# main.net
KiCad netlist of a schematic drawn in EAGLE
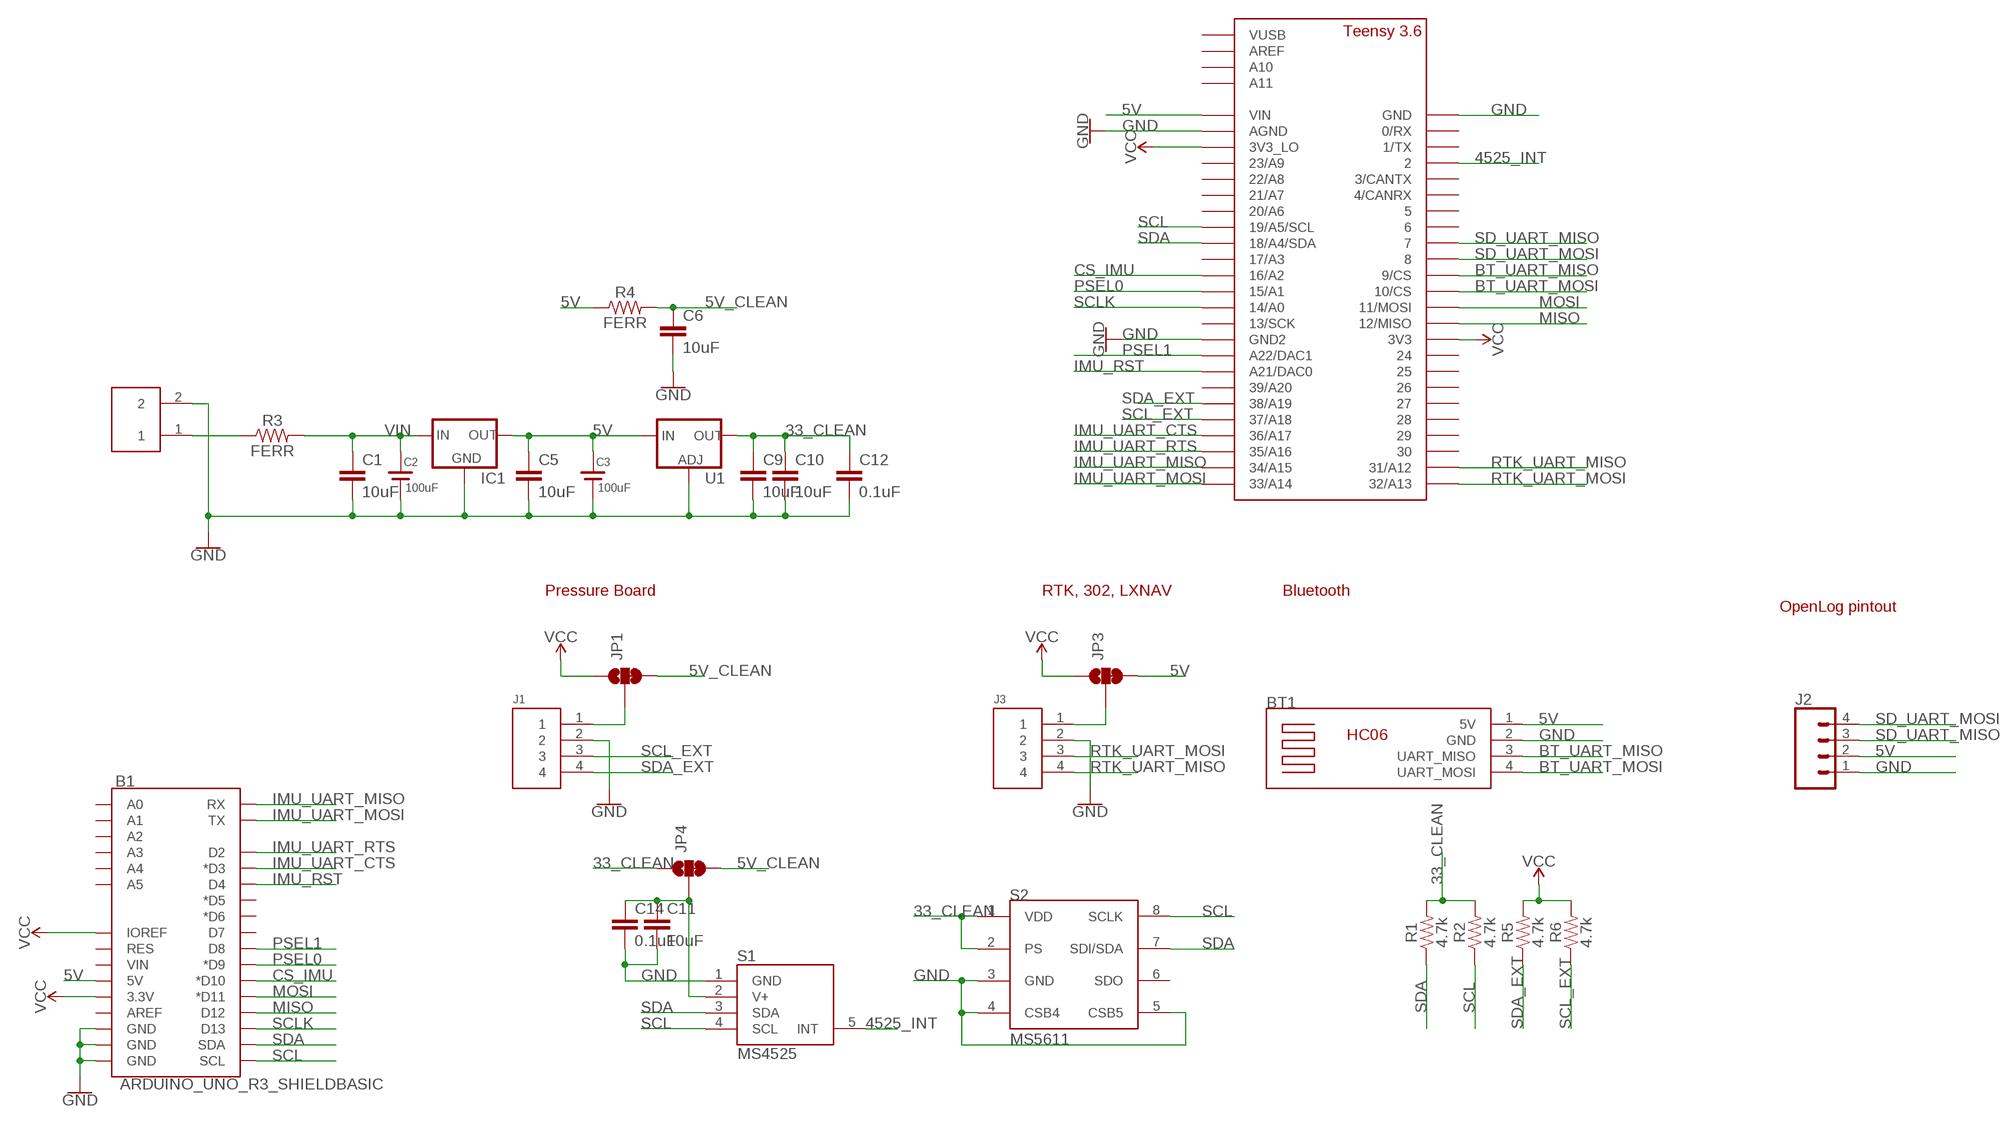
[diagram p0: schematic, sheet 1]

(export (version "E")
  (design (tool "Eeschema 10.0.6"))
  (components
    (comp (ref "B1")
      (value "ARDUINO_UNO_R3_SHIELDBASIC")
      (footprint "eagle-import:UNO_R3_SHIELD")
      (libsource (lib "eagle-import") (part "ARDUINO_UNO_R3_SHIELDBASIC"))
    )
    (comp (ref "BT1")
      (value "HC06")
      (footprint "eagle-import:HC06")
      (libsource (lib "eagle-import") (part "HC06"))
    )
    (comp (ref "C1")
      (value "10uF")
      (footprint "eagle-import:1206")
      (libsource (lib "eagle-import") (part "10UF-1206-6.3V-20%"))
    )
    (comp (ref "C2")
      (value "100uF")
      (footprint "eagle-import:CAP_8MM_35MM")
      (libsource (lib "eagle-import") (part "CAP_POLARCAP_8_DIA_35_LEAD"))
    )
    (comp (ref "C3")
      (value "100uF")
      (footprint "eagle-import:CAP_8MM_35MM")
      (libsource (lib "eagle-import") (part "CAP_POLARCAP_8_DIA_35_LEAD"))
    )
    (comp (ref "C5")
      (value "10uF")
      (footprint "eagle-import:1206")
      (libsource (lib "eagle-import") (part "10UF-1206-6.3V-20%"))
    )
    (comp (ref "C6")
      (value "10uF")
      (footprint "eagle-import:1206")
      (libsource (lib "eagle-import") (part "10UF-1206-6.3V-20%"))
    )
    (comp (ref "C9")
      (value "10uF")
      (footprint "eagle-import:1206")
      (libsource (lib "eagle-import") (part "10UF-1206-6.3V-20%"))
    )
    (comp (ref "C10")
      (value "10uF")
      (footprint "eagle-import:1206")
      (libsource (lib "eagle-import") (part "10UF-1206-6.3V-20%"))
    )
    (comp (ref "C11")
      (value "10uF")
      (footprint "eagle-import:1206")
      (libsource (lib "eagle-import") (part "10UF-1206-6.3V-20%"))
    )
    (comp (ref "C12")
      (value "0.1uF")
      (footprint "eagle-import:0603")
      (libsource (lib "eagle-import") (part "0.1UF-0603-25V-5%"))
    )
    (comp (ref "C14")
      (value "0.1uF")
      (footprint "eagle-import:0603")
      (libsource (lib "eagle-import") (part "0.1UF-0603-25V-5%"))
    )
    (comp (ref "IC1")
      (value "V_REG_78XXR-78E")
      (footprint "eagle-import:V78W")
      (libsource (lib "eagle-import") (part "V_REG_78XXR-78E"))
    )
    (comp (ref "J1")
      (value "HEADER4VALULOK")
      (footprint "eagle-import:4PINVALULOK")
      (libsource (lib "eagle-import") (part "HEADER4VALULOK"))
    )
    (comp (ref "J2")
      (value "CONN_04")
      (footprint "eagle-import:1X04")
      (libsource (lib "eagle-import") (part "CONN_04"))
    )
    (comp (ref "J3")
      (value "HEADER4VALULOK")
      (footprint "eagle-import:4PINVALULOK")
      (libsource (lib "eagle-import") (part "HEADER4VALULOK"))
    )
    (comp (ref "JP1")
      (value "JUMPER-SMT_3_1-NC_TRACE_SILK")
      (footprint "eagle-import:SMT-JUMPER_3_1-NC_TRACE_SILK")
      (libsource (lib "eagle-import") (part "JUMPER-SMT_3_1-NC_TRACE_SILK"))
    )
    (comp (ref "JP3")
      (value "JUMPER-SMT_3_1-NC_TRACE_SILK")
      (footprint "eagle-import:SMT-JUMPER_3_1-NC_TRACE_SILK")
      (libsource (lib "eagle-import") (part "JUMPER-SMT_3_1-NC_TRACE_SILK"))
    )
    (comp (ref "JP4")
      (value "JUMPER-SMT_3_1-NC_TRACE_SILK")
      (footprint "eagle-import:SMT-JUMPER_3_1-NC_TRACE_SILK")
      (libsource (lib "eagle-import") (part "JUMPER-SMT_3_1-NC_TRACE_SILK"))
    )
    (comp (ref "R1")
      (value "4.7k")
      (footprint "eagle-import:0603")
      (libsource (lib "eagle-import") (part "4.7KOHM-0603-1/10W-1%"))
    )
    (comp (ref "R2")
      (value "4.7k")
      (footprint "eagle-import:0603")
      (libsource (lib "eagle-import") (part "4.7KOHM-0603-1/10W-1%"))
    )
    (comp (ref "R3")
      (value "FERR")
      (footprint "eagle-import:1206")
      (libsource (lib "eagle-import") (part "RESISTOR1206"))
    )
    (comp (ref "R4")
      (value "FERR")
      (footprint "eagle-import:1206")
      (libsource (lib "eagle-import") (part "RESISTOR1206"))
    )
    (comp (ref "R5")
      (value "4.7k")
      (footprint "eagle-import:0603")
      (libsource (lib "eagle-import") (part "4.7KOHM-0603-1/10W-1%"))
    )
    (comp (ref "R6")
      (value "4.7k")
      (footprint "eagle-import:0603")
      (libsource (lib "eagle-import") (part "4.7KOHM-0603-1/10W-1%"))
    )
    (comp (ref "S1")
      (value "MS4525")
      (footprint "eagle-import:DIP1270W53P254L990H762Q8B")
      (libsource (lib "eagle-import") (part "MS4525MS4525DO"))
    )
    (comp (ref "S2")
      (value "MS5611")
      (footprint "eagle-import:MS5611")
      (libsource (lib "eagle-import") (part "MS5611"))
    )
    (comp (ref "U$1")
      (value "TEENSY_3.5/3.6_BASIC")
      (footprint "eagle-import:TEENSY_3.5_3.6_BASIC")
      (libsource (lib "eagle-import") (part "TEENSY_3.5/3.6_BASIC"))
    )
    (comp (ref "U$3")
      (value "HEADER2")
      (footprint "eagle-import:2PINVALULOK")
      (libsource (lib "eagle-import") (part "HEADER2"))
    )
    (comp (ref "U1")
      (value "V_REG_317SMD")
      (footprint "eagle-import:SOT223")
      (libsource (lib "eagle-import") (part "V_REG_317SMD"))
    )
  )
  (nets
    (net (code "1") (name "/5V") (class "Default")
      (node (ref "B1") (pin "5V") (pinfunction "5V_5V") (pintype "bidirectional"))
      (node (ref "BT1") (pin "1") (pinfunction "5V_1") (pintype "bidirectional"))
      (node (ref "C3") (pin "POS") (pinfunction "+_POS") (pintype "bidirectional"))
      (node (ref "C5") (pin "1") (pinfunction "1_1") (pintype "passive"))
      (node (ref "IC1") (pin "OUT") (pinfunction "OUT_OUT") (pintype "output"))
      (node (ref "J2") (pin "2") (pinfunction "2_2") (pintype "passive"))
      (node (ref "JP3") (pin "3") (pinfunction "3_3") (pintype "passive"))
      (node (ref "R4") (pin "1") (pinfunction "1_1") (pintype "passive"))
      (node (ref "U$1") (pin "VIN") (pinfunction "VIN_VIN") (pintype "bidirectional"))
      (node (ref "U1") (pin "3") (pinfunction "IN_3") (pintype "input"))
    )
    (net (code "2") (name "/5V_CLEAN") (class "Default")
      (node (ref "C6") (pin "1") (pinfunction "1_1") (pintype "passive"))
      (node (ref "JP1") (pin "3") (pinfunction "3_3") (pintype "passive"))
      (node (ref "JP4") (pin "3") (pinfunction "3_3") (pintype "passive"))
      (node (ref "R4") (pin "2") (pinfunction "2_2") (pintype "passive"))
    )
    (net (code "3") (name "/33_CLEAN") (class "Default")
      (node (ref "C10") (pin "1") (pinfunction "1_1") (pintype "passive"))
      (node (ref "C12") (pin "1") (pinfunction "1_1") (pintype "passive"))
      (node (ref "C9") (pin "1") (pinfunction "1_1") (pintype "passive"))
      (node (ref "JP4") (pin "1") (pinfunction "1_1") (pintype "passive"))
      (node (ref "R1") (pin "2") (pinfunction "2_2") (pintype "passive"))
      (node (ref "R2") (pin "2") (pinfunction "2_2") (pintype "passive"))
      (node (ref "S2") (pin "1") (pinfunction "VDD_1") (pintype "bidirectional"))
      (node (ref "S2") (pin "2") (pinfunction "PS_2") (pintype "bidirectional"))
      (node (ref "U1") (pin "2") (pinfunction "OUT_2") (pintype "output"))
    )
    (net (code "4") (name "/4525_INT") (class "Default")
      (node (ref "S1") (pin "5") (pinfunction "INT_5") (pintype "bidirectional"))
      (node (ref "U$1") (pin "2") (pinfunction "2_2") (pintype "bidirectional"))
    )
    (net (code "5") (name "/BT_UART_MISO") (class "Default")
      (node (ref "BT1") (pin "3") (pinfunction "UART_MISO_3") (pintype "bidirectional"))
      (node (ref "U$1") (pin "9/CS") (pinfunction "9/CS_9/CS") (pintype "bidirectional"))
    )
    (net (code "6") (name "/BT_UART_MOSI") (class "Default")
      (node (ref "BT1") (pin "4") (pinfunction "UART_MOSI_4") (pintype "bidirectional"))
      (node (ref "U$1") (pin "10/CS") (pinfunction "10/CS_10/CS") (pintype "bidirectional"))
    )
    (net (code "7") (name "/CS_IMU") (class "Default")
      (node (ref "B1") (pin "D10") (pinfunction "*D10_D10") (pintype "bidirectional"))
      (node (ref "U$1") (pin "16/A2") (pinfunction "16/A2_16/A2") (pintype "bidirectional"))
    )
    (net (code "8") (name "/IMU_RST") (class "Default")
      (node (ref "B1") (pin "D4") (pinfunction "D4_D4") (pintype "bidirectional"))
      (node (ref "U$1") (pin "21/DAC0") (pinfunction "A21/DAC0_21/DAC0") (pintype "bidirectional"))
    )
    (net (code "9") (name "/IMU_UART_CTS") (class "Default")
      (node (ref "B1") (pin "D3") (pinfunction "*D3_D3") (pintype "bidirectional"))
      (node (ref "U$1") (pin "36/A17") (pinfunction "36/A17_36/A17") (pintype "bidirectional"))
    )
    (net (code "10") (name "/IMU_UART_MISO") (class "Default")
      (node (ref "B1") (pin "RX") (pinfunction "RX_RX") (pintype "bidirectional"))
      (node (ref "U$1") (pin "34/A15") (pinfunction "34/A15_34/A15") (pintype "bidirectional"))
    )
    (net (code "11") (name "/IMU_UART_MOSI") (class "Default")
      (node (ref "B1") (pin "TX") (pinfunction "TX_TX") (pintype "bidirectional"))
      (node (ref "U$1") (pin "33/A14") (pinfunction "33/A14_33/A14") (pintype "bidirectional"))
    )
    (net (code "12") (name "/IMU_UART_RTS") (class "Default")
      (node (ref "B1") (pin "D2") (pinfunction "D2_D2") (pintype "bidirectional"))
      (node (ref "U$1") (pin "35/A16") (pinfunction "35/A16_35/A16") (pintype "bidirectional"))
    )
    (net (code "13") (name "/MISO") (class "Default")
      (node (ref "B1") (pin "D12") (pinfunction "D12_D12") (pintype "bidirectional"))
      (node (ref "U$1") (pin "12/MISO") (pinfunction "12/MISO_12/MISO") (pintype "bidirectional"))
    )
    (net (code "14") (name "/MOSI") (class "Default")
      (node (ref "B1") (pin "D11") (pinfunction "*D11_D11") (pintype "bidirectional"))
      (node (ref "U$1") (pin "11/MOSI") (pinfunction "11/MOSI_11/MOSI") (pintype "bidirectional"))
    )
    (net (code "15") (name "/PSEL0") (class "Default")
      (node (ref "B1") (pin "D9") (pinfunction "*D9_D9") (pintype "bidirectional"))
      (node (ref "U$1") (pin "15/A1") (pinfunction "15/A1_15/A1") (pintype "bidirectional"))
    )
    (net (code "16") (name "/PSEL1") (class "Default")
      (node (ref "B1") (pin "D8") (pinfunction "D8_D8") (pintype "bidirectional"))
      (node (ref "U$1") (pin "A22/DAC1") (pinfunction "A22/DAC1_A22/DAC1") (pintype "bidirectional"))
    )
    (net (code "17") (name "/RTK_UART_MISO") (class "Default")
      (node (ref "J3") (pin "4") (pinfunction "4_4") (pintype "bidirectional"))
      (node (ref "U$1") (pin "31/A12") (pinfunction "31/A12_31/A12") (pintype "bidirectional"))
    )
    (net (code "18") (name "/RTK_UART_MOSI") (class "Default")
      (node (ref "J3") (pin "3") (pinfunction "3_3") (pintype "bidirectional"))
      (node (ref "U$1") (pin "32/A13") (pinfunction "32/A13_32/A13") (pintype "bidirectional"))
    )
    (net (code "19") (name "/SCL") (class "Default")
      (node (ref "B1") (pin "SCL") (pinfunction "SCL_SCL") (pintype "bidirectional"))
      (node (ref "R2") (pin "1") (pinfunction "1_1") (pintype "passive"))
      (node (ref "S1") (pin "4") (pinfunction "SCL_4") (pintype "bidirectional"))
      (node (ref "S2") (pin "8") (pinfunction "SCLK_8") (pintype "bidirectional"))
      (node (ref "U$1") (pin "19/A5/SCL") (pinfunction "19/A5/SCL_19/A5/SCL") (pintype "bidirectional"))
    )
    (net (code "20") (name "/SCLK") (class "Default")
      (node (ref "B1") (pin "D13") (pinfunction "D13_D13") (pintype "bidirectional"))
      (node (ref "U$1") (pin "14/A0") (pinfunction "14/A0_14/A0") (pintype "bidirectional"))
    )
    (net (code "21") (name "/SCL_EXT") (class "Default")
      (node (ref "J1") (pin "3") (pinfunction "3_3") (pintype "bidirectional"))
      (node (ref "R6") (pin "1") (pinfunction "1_1") (pintype "passive"))
      (node (ref "U$1") (pin "37/A18") (pinfunction "37/A18_37/A18") (pintype "bidirectional"))
    )
    (net (code "22") (name "/SDA") (class "Default")
      (node (ref "B1") (pin "SDA") (pinfunction "SDA_SDA") (pintype "bidirectional"))
      (node (ref "R1") (pin "1") (pinfunction "1_1") (pintype "passive"))
      (node (ref "S1") (pin "3") (pinfunction "SDA_3") (pintype "bidirectional"))
      (node (ref "S2") (pin "7") (pinfunction "SDI/SDA_7") (pintype "bidirectional"))
      (node (ref "U$1") (pin "18/A4/SDA") (pinfunction "18/A4/SDA_18/A4/SDA") (pintype "bidirectional"))
    )
    (net (code "23") (name "/SDA_EXT") (class "Default")
      (node (ref "J1") (pin "4") (pinfunction "4_4") (pintype "bidirectional"))
      (node (ref "R5") (pin "1") (pinfunction "1_1") (pintype "passive"))
      (node (ref "U$1") (pin "38/A19") (pinfunction "38/A19_38/A19") (pintype "bidirectional"))
    )
    (net (code "24") (name "/SD_UART_MISO") (class "Default")
      (node (ref "J2") (pin "3") (pinfunction "3_3") (pintype "passive"))
      (node (ref "U$1") (pin "7") (pinfunction "7_7") (pintype "bidirectional"))
    )
    (net (code "25") (name "/SD_UART_MOSI") (class "Default")
      (node (ref "J2") (pin "4") (pinfunction "4_4") (pintype "passive"))
      (node (ref "U$1") (pin "8") (pinfunction "8_8") (pintype "bidirectional"))
    )
    (net (code "26") (name "/VIN") (class "Default")
      (node (ref "C1") (pin "1") (pinfunction "1_1") (pintype "passive"))
      (node (ref "C2") (pin "POS") (pinfunction "+_POS") (pintype "bidirectional"))
      (node (ref "IC1") (pin "IN") (pinfunction "IN_IN") (pintype "input"))
      (node (ref "R3") (pin "2") (pinfunction "2_2") (pintype "passive"))
    )
    (net (code "27") (name "GND") (class "Default")
      (node (ref "B1") (pin "GND@0") (pinfunction "GND_GND@0") (pintype "bidirectional"))
      (node (ref "B1") (pin "GND@1") (pinfunction "GND_GND@1") (pintype "bidirectional"))
      (node (ref "B1") (pin "GND@2") (pinfunction "GND_GND@2") (pintype "bidirectional"))
      (node (ref "BT1") (pin "2") (pinfunction "GND_2") (pintype "bidirectional"))
      (node (ref "C1") (pin "2") (pinfunction "2_2") (pintype "passive"))
      (node (ref "C10") (pin "2") (pinfunction "2_2") (pintype "passive"))
      (node (ref "C11") (pin "2") (pinfunction "2_2") (pintype "passive"))
      (node (ref "C12") (pin "2") (pinfunction "2_2") (pintype "passive"))
      (node (ref "C14") (pin "2") (pinfunction "2_2") (pintype "passive"))
      (node (ref "C2") (pin "NEG") (pinfunction "-_NEG") (pintype "bidirectional"))
      (node (ref "C3") (pin "NEG") (pinfunction "-_NEG") (pintype "bidirectional"))
      (node (ref "C5") (pin "2") (pinfunction "2_2") (pintype "passive"))
      (node (ref "C6") (pin "2") (pinfunction "2_2") (pintype "passive"))
      (node (ref "C9") (pin "2") (pinfunction "2_2") (pintype "passive"))
      (node (ref "IC1") (pin "GND") (pinfunction "GND_GND") (pintype "input"))
      (node (ref "J1") (pin "2") (pinfunction "2_2") (pintype "bidirectional"))
      (node (ref "J2") (pin "1") (pinfunction "1_1") (pintype "passive"))
      (node (ref "J3") (pin "2") (pinfunction "2_2") (pintype "bidirectional"))
      (node (ref "S1") (pin "1") (pinfunction "GND_1") (pintype "bidirectional"))
      (node (ref "S2") (pin "3") (pinfunction "GND_3") (pintype "bidirectional"))
      (node (ref "S2") (pin "4") (pinfunction "CSB4_4") (pintype "bidirectional"))
      (node (ref "S2") (pin "5") (pinfunction "CSB5_5") (pintype "bidirectional"))
      (node (ref "U$1") (pin "AGND") (pinfunction "AGND_AGND") (pintype "bidirectional"))
      (node (ref "U$1") (pin "GND") (pinfunction "GND_GND") (pintype "bidirectional"))
      (node (ref "U$1") (pin "GND2") (pinfunction "GND2_GND2") (pintype "bidirectional"))
      (node (ref "U$3") (pin "2") (pinfunction "2_2") (pintype "bidirectional"))
      (node (ref "U1") (pin "1") (pinfunction "ADJ_1") (pintype "input"))
    )
    (net (code "28") (name "Net-(J1-Pad1)") (class "Default")
      (node (ref "J1") (pin "1") (pinfunction "1_1") (pintype "bidirectional"))
      (node (ref "JP1") (pin "2") (pinfunction "2_2") (pintype "passive"))
    )
    (net (code "29") (name "Net-(J3-Pad1)") (class "Default")
      (node (ref "J3") (pin "1") (pinfunction "1_1") (pintype "bidirectional"))
      (node (ref "JP3") (pin "2") (pinfunction "2_2") (pintype "passive"))
    )
    (net (code "30") (name "Net-(R3-Pad1)") (class "Default")
      (node (ref "R3") (pin "1") (pinfunction "1_1") (pintype "passive"))
      (node (ref "U$3") (pin "1") (pinfunction "1_1") (pintype "bidirectional"))
    )
    (net (code "31") (name "Net-(S1-V+)") (class "Default")
      (node (ref "C11") (pin "1") (pinfunction "1_1") (pintype "passive"))
      (node (ref "C14") (pin "1") (pinfunction "1_1") (pintype "passive"))
      (node (ref "JP4") (pin "2") (pinfunction "2_2") (pintype "passive"))
      (node (ref "S1") (pin "2") (pinfunction "V+_2") (pintype "bidirectional"))
    )
    (net (code "32") (name "VCC") (class "Default")
      (node (ref "B1") (pin "3.3V") (pinfunction "3.3V_3.3V") (pintype "bidirectional"))
      (node (ref "B1") (pin "IOREF") (pinfunction "IOREF_IOREF") (pintype "bidirectional"))
      (node (ref "JP1") (pin "1") (pinfunction "1_1") (pintype "passive"))
      (node (ref "JP3") (pin "1") (pinfunction "1_1") (pintype "passive"))
      (node (ref "R5") (pin "2") (pinfunction "2_2") (pintype "passive"))
      (node (ref "R6") (pin "2") (pinfunction "2_2") (pintype "passive"))
      (node (ref "U$1") (pin "3V3") (pinfunction "3V3_3V3") (pintype "bidirectional"))
      (node (ref "U$1") (pin "3V3_LO") (pinfunction "3V3_LO_3V3_LO") (pintype "bidirectional"))
    )
    (net (code "33") (name "unconnected-(B1-*D5-PadD5)") (class "Default")
      (node (ref "B1") (pin "D5") (pinfunction "*D5_D5") (pintype "bidirectional"))
    )
    (net (code "34") (name "unconnected-(B1-*D6-PadD6)") (class "Default")
      (node (ref "B1") (pin "D6") (pinfunction "*D6_D6") (pintype "bidirectional"))
    )
    (net (code "35") (name "unconnected-(B1-PadA0)") (class "Default")
      (node (ref "B1") (pin "A0") (pinfunction "A0_A0") (pintype "bidirectional"))
    )
    (net (code "36") (name "unconnected-(B1-PadA1)") (class "Default")
      (node (ref "B1") (pin "A1") (pinfunction "A1_A1") (pintype "bidirectional"))
    )
    (net (code "37") (name "unconnected-(B1-PadA2)") (class "Default")
      (node (ref "B1") (pin "A2") (pinfunction "A2_A2") (pintype "bidirectional"))
    )
    (net (code "38") (name "unconnected-(B1-PadA3)") (class "Default")
      (node (ref "B1") (pin "A3") (pinfunction "A3_A3") (pintype "bidirectional"))
    )
    (net (code "39") (name "unconnected-(B1-PadA4)") (class "Default")
      (node (ref "B1") (pin "A4") (pinfunction "A4_A4") (pintype "bidirectional"))
    )
    (net (code "40") (name "unconnected-(B1-PadA5)") (class "Default")
      (node (ref "B1") (pin "A5") (pinfunction "A5_A5") (pintype "bidirectional"))
    )
    (net (code "41") (name "unconnected-(B1-PadAREF)") (class "Default")
      (node (ref "B1") (pin "AREF") (pinfunction "AREF_AREF") (pintype "bidirectional"))
    )
    (net (code "42") (name "unconnected-(B1-PadD7)") (class "Default")
      (node (ref "B1") (pin "D7") (pinfunction "D7_D7") (pintype "bidirectional"))
    )
    (net (code "43") (name "unconnected-(B1-PadRES)") (class "Default")
      (node (ref "B1") (pin "RES") (pinfunction "RES_RES") (pintype "bidirectional"))
    )
    (net (code "44") (name "unconnected-(B1-PadVIN)") (class "Default")
      (node (ref "B1") (pin "VIN") (pinfunction "VIN_VIN") (pintype "bidirectional"))
    )
    (net (code "45") (name "unconnected-(S2-SDO-Pad6)") (class "Default")
      (node (ref "S2") (pin "6") (pinfunction "SDO_6") (pintype "bidirectional"))
    )
    (net (code "46") (name "unconnected-(U$1-Pad0{slash}RX)") (class "Default")
      (node (ref "U$1") (pin "0/RX") (pinfunction "0/RX_0/RX") (pintype "bidirectional"))
    )
    (net (code "47") (name "unconnected-(U$1-Pad1{slash}TX)") (class "Default")
      (node (ref "U$1") (pin "1/TX") (pinfunction "1/TX_1/TX") (pintype "bidirectional"))
    )
    (net (code "48") (name "unconnected-(U$1-Pad3{slash}CANTX)") (class "Default")
      (node (ref "U$1") (pin "3/CANTX") (pinfunction "3/CANTX_3/CANTX") (pintype "bidirectional"))
    )
    (net (code "49") (name "unconnected-(U$1-Pad4{slash}CANRX)") (class "Default")
      (node (ref "U$1") (pin "4/CANRX") (pinfunction "4/CANRX_4/CANRX") (pintype "bidirectional"))
    )
    (net (code "50") (name "unconnected-(U$1-Pad5)") (class "Default")
      (node (ref "U$1") (pin "5") (pinfunction "5_5") (pintype "bidirectional"))
    )
    (net (code "51") (name "unconnected-(U$1-Pad6)") (class "Default")
      (node (ref "U$1") (pin "6") (pinfunction "6_6") (pintype "bidirectional"))
    )
    (net (code "52") (name "unconnected-(U$1-Pad13{slash}SCK)") (class "Default")
      (node (ref "U$1") (pin "13/SCK") (pinfunction "13/SCK_13/SCK") (pintype "bidirectional"))
    )
    (net (code "53") (name "unconnected-(U$1-Pad17{slash}A3)") (class "Default")
      (node (ref "U$1") (pin "17/A3") (pinfunction "17/A3_17/A3") (pintype "bidirectional"))
    )
    (net (code "54") (name "unconnected-(U$1-Pad20{slash}A6)") (class "Default")
      (node (ref "U$1") (pin "20/A6") (pinfunction "20/A6_20/A6") (pintype "bidirectional"))
    )
    (net (code "55") (name "unconnected-(U$1-Pad21{slash}A7)") (class "Default")
      (node (ref "U$1") (pin "21/A7") (pinfunction "21/A7_21/A7") (pintype "bidirectional"))
    )
    (net (code "56") (name "unconnected-(U$1-Pad22{slash}A8)") (class "Default")
      (node (ref "U$1") (pin "22/A8") (pinfunction "22/A8_22/A8") (pintype "bidirectional"))
    )
    (net (code "57") (name "unconnected-(U$1-Pad23{slash}A9)") (class "Default")
      (node (ref "U$1") (pin "23/A9") (pinfunction "23/A9_23/A9") (pintype "bidirectional"))
    )
    (net (code "58") (name "unconnected-(U$1-Pad24)") (class "Default")
      (node (ref "U$1") (pin "24") (pinfunction "24_24") (pintype "bidirectional"))
    )
    (net (code "59") (name "unconnected-(U$1-Pad25)") (class "Default")
      (node (ref "U$1") (pin "25") (pinfunction "25_25") (pintype "bidirectional"))
    )
    (net (code "60") (name "unconnected-(U$1-Pad26)") (class "Default")
      (node (ref "U$1") (pin "26") (pinfunction "26_26") (pintype "bidirectional"))
    )
    (net (code "61") (name "unconnected-(U$1-Pad27)") (class "Default")
      (node (ref "U$1") (pin "27") (pinfunction "27_27") (pintype "bidirectional"))
    )
    (net (code "62") (name "unconnected-(U$1-Pad28)") (class "Default")
      (node (ref "U$1") (pin "28") (pinfunction "28_28") (pintype "bidirectional"))
    )
    (net (code "63") (name "unconnected-(U$1-Pad29)") (class "Default")
      (node (ref "U$1") (pin "29") (pinfunction "29_29") (pintype "bidirectional"))
    )
    (net (code "64") (name "unconnected-(U$1-Pad30)") (class "Default")
      (node (ref "U$1") (pin "30") (pinfunction "30_30") (pintype "bidirectional"))
    )
    (net (code "65") (name "unconnected-(U$1-Pad39{slash}A20)") (class "Default")
      (node (ref "U$1") (pin "39/A20") (pinfunction "39/A20_39/A20") (pintype "bidirectional"))
    )
    (net (code "66") (name "unconnected-(U$1-PadA10)") (class "Default")
      (node (ref "U$1") (pin "A10") (pinfunction "A10_A10") (pintype "bidirectional"))
    )
    (net (code "67") (name "unconnected-(U$1-PadA11)") (class "Default")
      (node (ref "U$1") (pin "A11") (pinfunction "A11_A11") (pintype "bidirectional"))
    )
    (net (code "68") (name "unconnected-(U$1-PadAREF)") (class "Default")
      (node (ref "U$1") (pin "AREF") (pinfunction "AREF_AREF") (pintype "bidirectional"))
    )
    (net (code "69") (name "unconnected-(U$1-PadVUSB)") (class "Default")
      (node (ref "U$1") (pin "VUSB") (pinfunction "VUSB_VUSB") (pintype "bidirectional"))
    )
  )
)
